# Domino_Pi.net
KiCad netlist of a schematic drawn in EAGLE
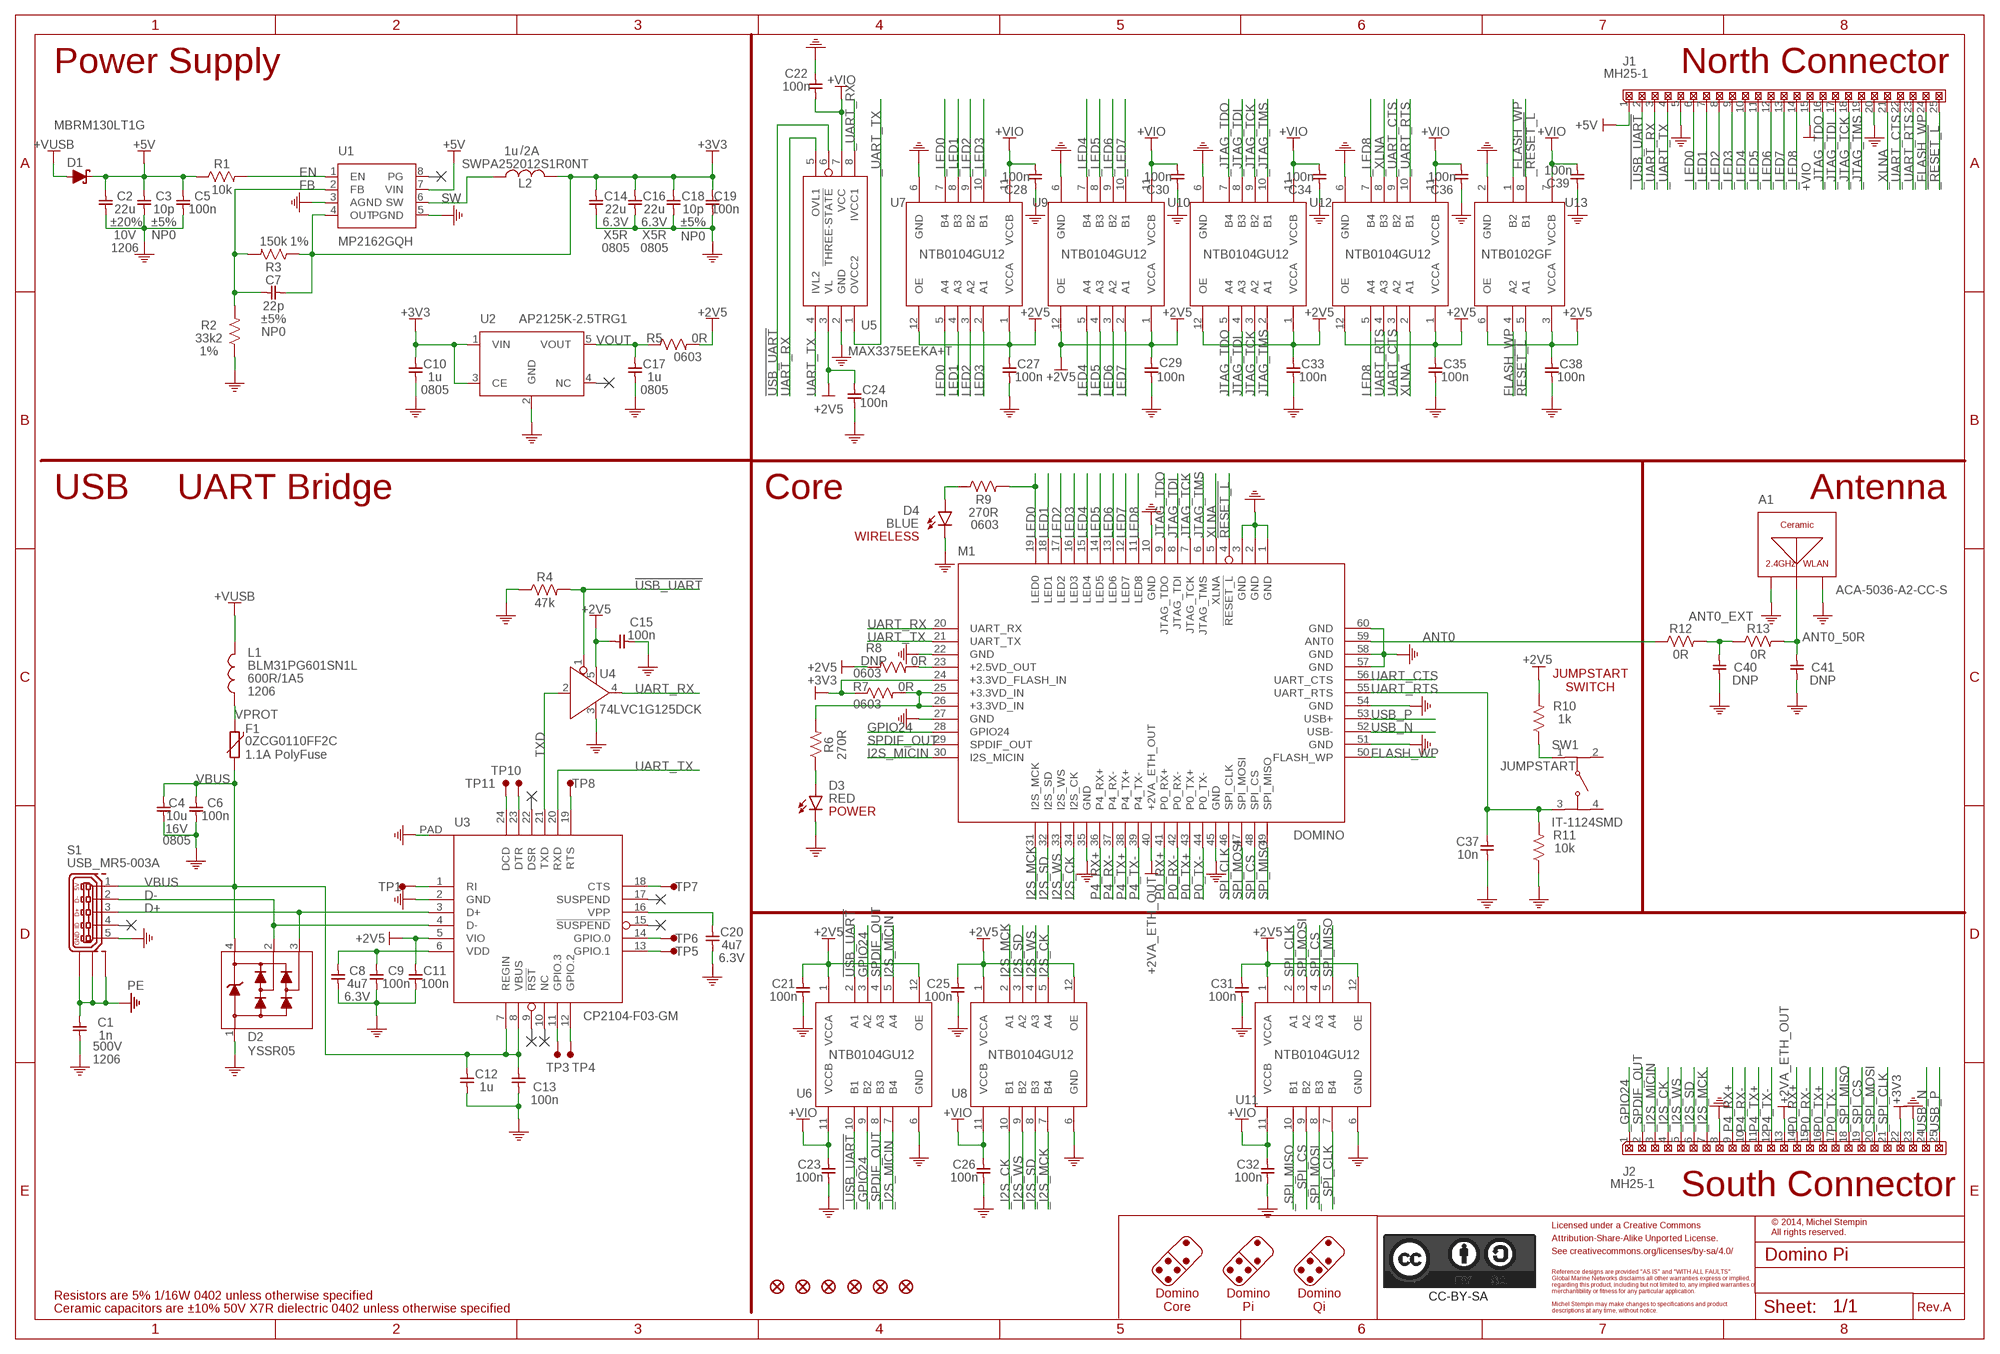
[diagram p0: schematic, sheet 1]

(export (version "E")
  (design (tool "Eeschema 10.0.6"))
  (components
    (comp (ref "A1")
      (value "ACA-5036-A2-CC-S")
      (footprint "eagle-import:ACA-5036-A2-CC-S")
      (libsource (lib "eagle-import") (part "ACA-5036-A2-CC-S"))
    )
    (comp (ref "C1")
      (value "1n")
      (footprint "eagle-import:C1206")
      (fields
        (field (name "SIZE") "1206")
        (field (name "PARTNO") "C1206_1n_X7R_10%_CER_500V")
        (field (name "VOLT") "500V")
      )
      (libsource (lib "eagle-import") (part "CAP_1206"))
    )
    (comp (ref "C2")
      (value "22u")
      (footprint "eagle-import:C1206")
      (fields
        (field (name "SIZE") "1206")
        (field (name "PARTNO") "C1206_22u_X7R_20%_CER_10V")
        (field (name "TOL") "±20%")
        (field (name "VOLT") "10V")
      )
      (libsource (lib "eagle-import") (part "CAP_1206"))
    )
    (comp (ref "C3")
      (value "10p")
      (footprint "eagle-import:C0402")
      (fields
        (field (name "PARTNO") "C0402_10p_NP0_5%_CER_50V")
        (field (name "TC") "NP0")
        (field (name "TOL") "±5%")
      )
      (libsource (lib "eagle-import") (part "CAP_0402"))
    )
    (comp (ref "C4")
      (value "10u")
      (footprint "eagle-import:C0805")
      (fields
        (field (name "SIZE") "0805")
        (field (name "PARTNO") "C0805_10u_X7R_10%_CER_16V")
        (field (name "VOLT") "16V")
      )
      (libsource (lib "eagle-import") (part "CAP_0805"))
    )
    (comp (ref "C5")
      (value "100n")
      (footprint "eagle-import:C0402")
      (fields (field (name "PARTNO") "C0402_100n_X7R_10%_CER_50V"))
      (libsource (lib "eagle-import") (part "CAP_0402"))
    )
    (comp (ref "C6")
      (value "100n")
      (footprint "eagle-import:C0402")
      (fields (field (name "PARTNO") "C0402_100n_X7R_10%_CER_50V"))
      (libsource (lib "eagle-import") (part "CAP_0402"))
    )
    (comp (ref "C7")
      (value "22p")
      (footprint "eagle-import:C0402")
      (fields
        (field (name "PARTNO") "C0402_22p_NP0_5%_CER_50V")
        (field (name "TC") "NP0")
        (field (name "TOL") "±5%")
      )
      (libsource (lib "eagle-import") (part "CAP_0402"))
    )
    (comp (ref "C8")
      (value "4u7")
      (footprint "eagle-import:C0402")
      (fields (field (name "PARTNO") "C0402_4u7_X7R_10%_CER_6V3") (field (name "VOLT") "6.3V"))
      (libsource (lib "eagle-import") (part "CAP_0402"))
    )
    (comp (ref "C9")
      (value "100n")
      (footprint "eagle-import:C0402")
      (fields (field (name "PARTNO") "C0402_100n_X7R_10%_CER_50V"))
      (libsource (lib "eagle-import") (part "CAP_0402"))
    )
    (comp (ref "C10")
      (value "1u")
      (footprint "eagle-import:C0805")
      (fields (field (name "SIZE") "0805") (field (name "PARTNO") "C0805_1u_X7R_10%_CER_50V"))
      (libsource (lib "eagle-import") (part "CAP_0805"))
    )
    (comp (ref "C11")
      (value "100n")
      (footprint "eagle-import:C0402")
      (fields (field (name "PARTNO") "C0402_100n_X7R_10%_CER_50V"))
      (libsource (lib "eagle-import") (part "CAP_0402"))
    )
    (comp (ref "C12")
      (value "1u")
      (footprint "eagle-import:C0402")
      (fields (field (name "PARTNO") "C0402_1u_X7R_10%_CER_50V"))
      (libsource (lib "eagle-import") (part "CAP_0402"))
    )
    (comp (ref "C13")
      (value "100n")
      (footprint "eagle-import:C0402")
      (fields (field (name "PARTNO") "C0402_100n_X7R_10%_CER_50V"))
      (libsource (lib "eagle-import") (part "CAP_0402"))
    )
    (comp (ref "C14")
      (value "22u")
      (footprint "eagle-import:C0805")
      (fields
        (field (name "SIZE") "0805")
        (field (name "PARTNO") "C0805_22u_X5R_20%_CER_6V3")
        (field (name "TC") "X5R")
        (field (name "VOLT") "6.3V")
      )
      (libsource (lib "eagle-import") (part "CAP_0805"))
    )
    (comp (ref "C15")
      (value "100n")
      (footprint "eagle-import:C0402")
      (fields (field (name "PARTNO") "C0402_100n_X7R_10%_CER_50V"))
      (libsource (lib "eagle-import") (part "CAP_0402"))
    )
    (comp (ref "C16")
      (value "22u")
      (footprint "eagle-import:C0805")
      (fields
        (field (name "SIZE") "0805")
        (field (name "PARTNO") "C0805_22u_X5R_20%_CER_6V3")
        (field (name "TC") "X5R")
        (field (name "VOLT") "6.3V")
      )
      (libsource (lib "eagle-import") (part "CAP_0805"))
    )
    (comp (ref "C17")
      (value "1u")
      (footprint "eagle-import:C0805")
      (fields (field (name "SIZE") "0805") (field (name "PARTNO") "C0805_1u_X7R_10%_CER_50V"))
      (libsource (lib "eagle-import") (part "CAP_0805"))
    )
    (comp (ref "C18")
      (value "10p")
      (footprint "eagle-import:C0402")
      (fields
        (field (name "PARTNO") "C0402_10p_NP0_5%_CER_50V")
        (field (name "TC") "NP0")
        (field (name "TOL") "±5%")
      )
      (libsource (lib "eagle-import") (part "CAP_0402"))
    )
    (comp (ref "C19")
      (value "100n")
      (footprint "eagle-import:C0402")
      (fields (field (name "PARTNO") "C0402_100n_X7R_10%_CER_50V"))
      (libsource (lib "eagle-import") (part "CAP_0402"))
    )
    (comp (ref "C20")
      (value "4u7")
      (footprint "eagle-import:C0402")
      (fields (field (name "PARTNO") "C0402_4u7_X7R_10%_CER_6V3") (field (name "VOLT") "6.3V"))
      (libsource (lib "eagle-import") (part "CAP_0402"))
    )
    (comp (ref "C21")
      (value "100n")
      (footprint "eagle-import:C0402")
      (fields (field (name "PARTNO") "C0402_100n_X7R_10%_CER_50V"))
      (libsource (lib "eagle-import") (part "CAP_0402"))
    )
    (comp (ref "C22")
      (value "100n")
      (footprint "eagle-import:C0402")
      (fields (field (name "PARTNO") "C0402_100n_X7R_10%_CER_50V"))
      (libsource (lib "eagle-import") (part "CAP_0402"))
    )
    (comp (ref "C23")
      (value "100n")
      (footprint "eagle-import:C0402")
      (fields (field (name "PARTNO") "C0402_100n_X7R_10%_CER_50V"))
      (libsource (lib "eagle-import") (part "CAP_0402"))
    )
    (comp (ref "C24")
      (value "100n")
      (footprint "eagle-import:C0402")
      (fields (field (name "PARTNO") "C0402_100n_X7R_10%_CER_50V"))
      (libsource (lib "eagle-import") (part "CAP_0402"))
    )
    (comp (ref "C25")
      (value "100n")
      (footprint "eagle-import:C0402")
      (fields (field (name "PARTNO") "C0402_100n_X7R_10%_CER_50V"))
      (libsource (lib "eagle-import") (part "CAP_0402"))
    )
    (comp (ref "C26")
      (value "100n")
      (footprint "eagle-import:C0402")
      (fields (field (name "PARTNO") "C0402_100n_X7R_10%_CER_50V"))
      (libsource (lib "eagle-import") (part "CAP_0402"))
    )
    (comp (ref "C27")
      (value "100n")
      (footprint "eagle-import:C0402")
      (fields (field (name "PARTNO") "C0402_100n_X7R_10%_CER_50V"))
      (libsource (lib "eagle-import") (part "CAP_0402"))
    )
    (comp (ref "C28")
      (value "100n")
      (footprint "eagle-import:C0402")
      (fields (field (name "PARTNO") "C0402_100n_X7R_10%_CER_50V"))
      (libsource (lib "eagle-import") (part "CAP_0402"))
    )
    (comp (ref "C29")
      (value "100n")
      (footprint "eagle-import:C0402")
      (fields (field (name "PARTNO") "C0402_100n_X7R_10%_CER_50V"))
      (libsource (lib "eagle-import") (part "CAP_0402"))
    )
    (comp (ref "C30")
      (value "100n")
      (footprint "eagle-import:C0402")
      (fields (field (name "PARTNO") "C0402_100n_X7R_10%_CER_50V"))
      (libsource (lib "eagle-import") (part "CAP_0402"))
    )
    (comp (ref "C31")
      (value "100n")
      (footprint "eagle-import:C0402")
      (fields (field (name "PARTNO") "C0402_100n_X7R_10%_CER_50V"))
      (libsource (lib "eagle-import") (part "CAP_0402"))
    )
    (comp (ref "C32")
      (value "100n")
      (footprint "eagle-import:C0402")
      (fields (field (name "PARTNO") "C0402_100n_X7R_10%_CER_50V"))
      (libsource (lib "eagle-import") (part "CAP_0402"))
    )
    (comp (ref "C33")
      (value "100n")
      (footprint "eagle-import:C0402")
      (fields (field (name "PARTNO") "C0402_100n_X7R_10%_CER_50V"))
      (libsource (lib "eagle-import") (part "CAP_0402"))
    )
    (comp (ref "C34")
      (value "100n")
      (footprint "eagle-import:C0402")
      (fields (field (name "PARTNO") "C0402_100n_X7R_10%_CER_50V"))
      (libsource (lib "eagle-import") (part "CAP_0402"))
    )
    (comp (ref "C35")
      (value "100n")
      (footprint "eagle-import:C0402")
      (fields (field (name "PARTNO") "C0402_100n_X7R_10%_CER_50V"))
      (libsource (lib "eagle-import") (part "CAP_0402"))
    )
    (comp (ref "C36")
      (value "100n")
      (footprint "eagle-import:C0402")
      (fields (field (name "PARTNO") "C0402_100n_X7R_10%_CER_50V"))
      (libsource (lib "eagle-import") (part "CAP_0402"))
    )
    (comp (ref "C37")
      (value "10n")
      (footprint "eagle-import:C0402")
      (fields (field (name "PARTNO") "C0402_10n_X7R_10%_CER_50V"))
      (libsource (lib "eagle-import") (part "CAP_0402"))
    )
    (comp (ref "C38")
      (value "100n")
      (footprint "eagle-import:C0402")
      (fields (field (name "PARTNO") "C0402_100n_X7R_10%_CER_50V"))
      (libsource (lib "eagle-import") (part "CAP_0402"))
    )
    (comp (ref "C39")
      (value "100n")
      (footprint "eagle-import:C0402")
      (fields (field (name "PARTNO") "C0402_100n_X7R_10%_CER_50V"))
      (libsource (lib "eagle-import") (part "CAP_0402"))
    )
    (comp (ref "C40")
      (value "DNP")
      (footprint "eagle-import:C0402")
      (fields (field (name "PARTNO") "C0402_DNP"))
      (libsource (lib "eagle-import") (part "CAP_0402"))
    )
    (comp (ref "C41")
      (value "DNP")
      (footprint "eagle-import:C0402")
      (fields (field (name "PARTNO") "C0402_DNP"))
      (libsource (lib "eagle-import") (part "CAP_0402"))
    )
    (comp (ref "CC-BY-SA")
      (value "CC-BY-SA_LOGO")
      (footprint "eagle-import:CC-BY-SA_LOGO")
      (libsource (lib "eagle-import") (part "CC-BY-SA_LOGO"))
    )
    (comp (ref "D1")
      (value "MBRM130LT1G")
      (footprint "eagle-import:DO-216AA")
      (libsource (lib "eagle-import") (part "MBRM130LT1G"))
    )
    (comp (ref "D2")
      (value "YSSR05")
      (footprint "eagle-import:SOT143B")
      (libsource (lib "eagle-import") (part "YSSR05"))
    )
    (comp (ref "D3")
      (value "RED")
      (footprint "eagle-import:LED0603")
      (fields (field (name "PARTNO") "LED0603-RED"))
      (libsource (lib "eagle-import") (part "LED_0603"))
    )
    (comp (ref "D4")
      (value "BLUE")
      (footprint "eagle-import:LED0603")
      (fields (field (name "PARTNO") "LED0603-BLUE"))
      (libsource (lib "eagle-import") (part "LED_0603"))
    )
    (comp (ref "F1")
      (value "0ZCG0110FF2C")
      (footprint "eagle-import:PTC1812")
      (fields (field (name "RATE") "1.1A"))
      (libsource (lib "eagle-import") (part "0ZCG0110FF2C"))
    )
    (comp (ref "F2")
      (value "FIDUCIAL")
      (footprint "eagle-import:FIDUCIAL")
      (libsource (lib "eagle-import") (part "FIDUCIAL"))
    )
    (comp (ref "F3")
      (value "FIDUCIAL")
      (footprint "eagle-import:FIDUCIAL")
      (libsource (lib "eagle-import") (part "FIDUCIAL"))
    )
    (comp (ref "F4")
      (value "FIDUCIAL")
      (footprint "eagle-import:FIDUCIAL")
      (libsource (lib "eagle-import") (part "FIDUCIAL"))
    )
    (comp (ref "F5")
      (value "FIDUCIAL")
      (footprint "eagle-import:FIDUCIAL")
      (libsource (lib "eagle-import") (part "FIDUCIAL"))
    )
    (comp (ref "F6")
      (value "FIDUCIAL")
      (footprint "eagle-import:FIDUCIAL")
      (libsource (lib "eagle-import") (part "FIDUCIAL"))
    )
    (comp (ref "F7")
      (value "FIDUCIAL")
      (footprint "eagle-import:FIDUCIAL")
      (libsource (lib "eagle-import") (part "FIDUCIAL"))
    )
    (comp (ref "J1")
      (value "MH25-1")
      (footprint "eagle-import:MH25-1-0.1")
      (fields (field (name "PARTNO") "MH25-1-0.1"))
      (libsource (lib "eagle-import") (part "MH25-1"))
    )
    (comp (ref "J2")
      (value "MH25-1")
      (footprint "eagle-import:MH25-1-0.1")
      (fields (field (name "PARTNO") "MH25-1-0.1"))
      (libsource (lib "eagle-import") (part "MH25-1"))
    )
    (comp (ref "L1")
      (value "BLM31PG601SN1L")
      (footprint "eagle-import:FB1206")
      (fields (field (name "SIZE") "1206") (field (name "OPT") "600R/1A5"))
      (libsource (lib "eagle-import") (part "FB_1206"))
    )
    (comp (ref "L2")
      (value "SWPA252012S1R0NT")
      (footprint "eagle-import:SWPA252012S")
      (fields
        (field (name "INDUCTANCE") "1u")
        (field (name "RATE") "2A")
        (field (name "PARTNO") "SWPA252012SMT")
        (field (name "RATE_1") "2A")
      )
      (libsource (lib "eagle-import") (part "SWPA252012S?NT1R0"))
    )
    (comp (ref "M1")
      (value "DOMINO")
      (footprint "eagle-import:DOMINO")
      (fields (field (name "PARTNO") "DOMINO-CORE"))
      (libsource (lib "eagle-import") (part "DOMINO"))
    )
    (comp (ref "R1")
      (value "10k")
      (footprint "eagle-import:R0402")
      (fields (field (name "PARTNO") "R0402_10k_5%_62.5mW"))
      (libsource (lib "eagle-import") (part "RES_0402"))
    )
    (comp (ref "R2")
      (value "33k2")
      (footprint "eagle-import:R0402")
      (fields (field (name "PARTNO") "R0402_33k2_1%_62.5mW") (field (name "TOL") "1%"))
      (libsource (lib "eagle-import") (part "RES_0402"))
    )
    (comp (ref "R3")
      (value "150k")
      (footprint "eagle-import:R0402")
      (fields (field (name "PARTNO") "R0402_150k_1%_62.5mW") (field (name "TOL") "1%"))
      (libsource (lib "eagle-import") (part "RES_0402"))
    )
    (comp (ref "R4")
      (value "47k")
      (footprint "eagle-import:R0402")
      (fields (field (name "PARTNO") "R0402_47k_5%_62.5mW"))
      (libsource (lib "eagle-import") (part "RES_0402"))
    )
    (comp (ref "R5")
      (value "0R")
      (footprint "eagle-import:R0603")
      (fields (field (name "SIZE") "0603") (field (name "PARTNO") "R0603_0R_5%_125mW"))
      (libsource (lib "eagle-import") (part "RES_0603"))
    )
    (comp (ref "R6")
      (value "270R")
      (footprint "eagle-import:R0402")
      (fields (field (name "PARTNO") "R0603_270R_5%_125mW"))
      (libsource (lib "eagle-import") (part "RES_0402"))
    )
    (comp (ref "R7")
      (value "0R")
      (footprint "eagle-import:R0603")
      (fields (field (name "SIZE") "0603") (field (name "PARTNO") "R0603_0R_5%_125mW"))
      (libsource (lib "eagle-import") (part "RES_0603"))
    )
    (comp (ref "R8")
      (value "0R")
      (footprint "eagle-import:R0603")
      (fields (field (name "SIZE") "0603") (field (name "PARTNO") "R0603_0R_5%_125mW"))
      (libsource (lib "eagle-import") (part "RES_0603"))
    )
    (comp (ref "R9")
      (value "270R")
      (footprint "eagle-import:R0603")
      (fields (field (name "SIZE") "0603") (field (name "PARTNO") "R0603_270R_5%_125mW"))
      (libsource (lib "eagle-import") (part "RES_0603"))
    )
    (comp (ref "R10")
      (value "1k")
      (footprint "eagle-import:R0402")
      (fields (field (name "PARTNO") "R0402_1k_5%_62.5mW"))
      (libsource (lib "eagle-import") (part "RES_0402"))
    )
    (comp (ref "R11")
      (value "10k")
      (footprint "eagle-import:R0402")
      (fields (field (name "PARTNO") "R0402_10k_5%_62.5mW"))
      (libsource (lib "eagle-import") (part "RES_0402"))
    )
    (comp (ref "R12")
      (value "0R")
      (footprint "eagle-import:R0402")
      (fields (field (name "PARTNO") "R0402_0R_5%_62.5mW"))
      (libsource (lib "eagle-import") (part "RES_0402"))
    )
    (comp (ref "R13")
      (value "0R")
      (footprint "eagle-import:R0402")
      (fields (field (name "PARTNO") "R0402_0R_5%_62.5mW"))
      (libsource (lib "eagle-import") (part "RES_0402"))
    )
    (comp (ref "S1")
      (value "USB_MR5-003A")
      (footprint "eagle-import:USB_MR5-003A")
      (fields (field (name "PARTNO") "USB MR5-003A"))
      (libsource (lib "eagle-import") (part "USB_MR5-003A"))
    )
    (comp (ref "SW1")
      (value "IT-1124SMD")
      (footprint "eagle-import:IT-1124SMD")
      (libsource (lib "eagle-import") (part "IT-1124SMD"))
    )
    (comp (ref "TP1")
      (value "TEST_PAD")
      (footprint "eagle-import:TEST_PAD")
      (libsource (lib "eagle-import") (part "TEST_PAD"))
    )
    (comp (ref "TP3")
      (value "TEST_PAD")
      (footprint "eagle-import:TEST_PAD")
      (libsource (lib "eagle-import") (part "TEST_PAD"))
    )
    (comp (ref "TP4")
      (value "TEST_PAD")
      (footprint "eagle-import:TEST_PAD")
      (libsource (lib "eagle-import") (part "TEST_PAD"))
    )
    (comp (ref "TP5")
      (value "TEST_PAD")
      (footprint "eagle-import:TEST_PAD")
      (libsource (lib "eagle-import") (part "TEST_PAD"))
    )
    (comp (ref "TP6")
      (value "TEST_PAD")
      (footprint "eagle-import:TEST_PAD")
      (libsource (lib "eagle-import") (part "TEST_PAD"))
    )
    (comp (ref "TP7")
      (value "TEST_PAD")
      (footprint "eagle-import:TEST_PAD")
      (libsource (lib "eagle-import") (part "TEST_PAD"))
    )
    (comp (ref "TP8")
      (value "TEST_PAD")
      (footprint "eagle-import:TEST_PAD")
      (libsource (lib "eagle-import") (part "TEST_PAD"))
    )
    (comp (ref "TP10")
      (value "TEST_PAD")
      (footprint "eagle-import:TEST_PAD")
      (libsource (lib "eagle-import") (part "TEST_PAD"))
    )
    (comp (ref "TP11")
      (value "TEST_PAD")
      (footprint "eagle-import:TEST_PAD")
      (libsource (lib "eagle-import") (part "TEST_PAD"))
    )
    (comp (ref "U1")
      (value "MP2162GQH")
      (footprint "eagle-import:QFN-8_2X1.5")
      (libsource (lib "eagle-import") (part "MP2162GQH"))
    )
    (comp (ref "U2")
      (value "AP2125K-2.5TRG1")
      (footprint "eagle-import:SOT23-5")
      (libsource (lib "eagle-import") (part "AP2125?K-2.5TRG1"))
    )
    (comp (ref "U3")
      (value "CP2104-F03-GM")
      (footprint "eagle-import:QFN-25_4X4")
      (libsource (lib "eagle-import") (part "CP2104-F03-GM"))
    )
    (comp (ref "U4")
      (value "74LVC1G125DCK")
      (footprint "eagle-import:SC70")
      (fields (field (name "PARTNO") "74LVC1G125DCK "))
      (libsource (lib "eagle-import") (part "741G125DCKLVC"))
    )
    (comp (ref "U5")
      (value "MAX3375EEKA+T")
      (footprint "eagle-import:SOT23-8")
      (libsource (lib "eagle-import") (part "MAX3375EEKA+T"))
    )
    (comp (ref "U6")
      (value "NTB0104GU12")
      (footprint "eagle-import:XQFN-12")
      (libsource (lib "eagle-import") (part "NTB0104GU12"))
    )
    (comp (ref "U7")
      (value "NTB0104GU12")
      (footprint "eagle-import:XQFN-12")
      (libsource (lib "eagle-import") (part "NTB0104GU12"))
    )
    (comp (ref "U8")
      (value "NTB0104GU12")
      (footprint "eagle-import:XQFN-12")
      (libsource (lib "eagle-import") (part "NTB0104GU12"))
    )
    (comp (ref "U9")
      (value "NTB0104GU12")
      (footprint "eagle-import:XQFN-12")
      (libsource (lib "eagle-import") (part "NTB0104GU12"))
    )
    (comp (ref "U10")
      (value "NTB0104GU12")
      (footprint "eagle-import:XQFN-12")
      (libsource (lib "eagle-import") (part "NTB0104GU12"))
    )
    (comp (ref "U11")
      (value "NTB0104GU12")
      (footprint "eagle-import:XQFN-12")
      (libsource (lib "eagle-import") (part "NTB0104GU12"))
    )
    (comp (ref "U12")
      (value "NTB0104GU12")
      (footprint "eagle-import:XQFN-12")
      (libsource (lib "eagle-import") (part "NTB0104GU12"))
    )
    (comp (ref "U13")
      (value "NTB0102GF")
      (footprint "eagle-import:SOT1089")
      (libsource (lib "eagle-import") (part "NTB0102GF"))
    )
  )
  (nets
    (net (code "1") (name "+2V5") (class "Default")
      (node (ref "C11") (pin "1") (pinfunction "1_1") (pintype "passive"))
      (node (ref "C15") (pin "2") (pinfunction "2_2") (pintype "passive"))
      (node (ref "C21") (pin "1") (pinfunction "1_1") (pintype "passive"))
      (node (ref "C24") (pin "2") (pinfunction "2_2") (pintype "passive"))
      (node (ref "C25") (pin "1") (pinfunction "1_1") (pintype "passive"))
      (node (ref "C27") (pin "2") (pinfunction "2_2") (pintype "passive"))
      (node (ref "C29") (pin "2") (pinfunction "2_2") (pintype "passive"))
      (node (ref "C31") (pin "1") (pinfunction "1_1") (pintype "passive"))
      (node (ref "C33") (pin "2") (pinfunction "2_2") (pintype "passive"))
      (node (ref "C35") (pin "2") (pinfunction "2_2") (pintype "passive"))
      (node (ref "C38") (pin "2") (pinfunction "2_2") (pintype "passive"))
      (node (ref "R10") (pin "2") (pinfunction "2_2") (pintype "passive"))
      (node (ref "R5") (pin "2") (pinfunction "2_2") (pintype "passive"))
      (node (ref "R8") (pin "1") (pinfunction "1_1") (pintype "passive"))
      (node (ref "U10") (pin "1") (pinfunction "VCCA_1") (pintype "power_in"))
      (node (ref "U10") (pin "12") (pinfunction "OE_12") (pintype "input"))
      (node (ref "U11") (pin "1") (pinfunction "VCCA_1") (pintype "power_in"))
      (node (ref "U11") (pin "12") (pinfunction "OE_12") (pintype "input"))
      (node (ref "U12") (pin "1") (pinfunction "VCCA_1") (pintype "power_in"))
      (node (ref "U12") (pin "12") (pinfunction "OE_12") (pintype "input"))
      (node (ref "U13") (pin "3") (pinfunction "VCCA_3") (pintype "power_in"))
      (node (ref "U13") (pin "6") (pinfunction "OE_6") (pintype "input"))
      (node (ref "U3") (pin "5") (pinfunction "VIO_5") (pintype "power_in"))
      (node (ref "U4") (pin "5") (pinfunction "VCC_5") (pintype "power_in"))
      (node (ref "U5") (pin "3") (pinfunction "VL_3") (pintype "power_in"))
      (node (ref "U6") (pin "1") (pinfunction "VCCA_1") (pintype "power_in"))
      (node (ref "U6") (pin "12") (pinfunction "OE_12") (pintype "input"))
      (node (ref "U7") (pin "1") (pinfunction "VCCA_1") (pintype "power_in"))
      (node (ref "U7") (pin "12") (pinfunction "OE_12") (pintype "input"))
      (node (ref "U8") (pin "1") (pinfunction "VCCA_1") (pintype "power_in"))
      (node (ref "U8") (pin "12") (pinfunction "OE_12") (pintype "input"))
      (node (ref "U9") (pin "1") (pinfunction "VCCA_1") (pintype "power_in"))
      (node (ref "U9") (pin "12") (pinfunction "OE_12") (pintype "input"))
    )
    (net (code "2") (name "+2VA_ETH_OUT") (class "Default")
      (node (ref "J2") (pin "13") (pinfunction "13_13") (pintype "passive"))
      (node (ref "M1") (pin "40") (pinfunction "+2VA_ETH_OUT_40") (pintype "power_in"))
    )
    (net (code "3") (name "+3V3") (class "Default")
      (node (ref "C10") (pin "1") (pinfunction "1_1") (pintype "passive"))
      (node (ref "C14") (pin "1") (pinfunction "1_1") (pintype "passive"))
      (node (ref "C16") (pin "1") (pinfunction "1_1") (pintype "passive"))
      (node (ref "C18") (pin "1") (pinfunction "1_1") (pintype "passive"))
      (node (ref "C19") (pin "1") (pinfunction "1_1") (pintype "passive"))
      (node (ref "C7") (pin "2") (pinfunction "2_2") (pintype "passive"))
      (node (ref "J2") (pin "22") (pinfunction "22_22") (pintype "passive"))
      (node (ref "L2") (pin "2") (pinfunction "2_2") (pintype "passive"))
      (node (ref "M1") (pin "24") (pinfunction "+3.3VD_FLASH_IN_24") (pintype "power_in"))
      (node (ref "R3") (pin "1") (pinfunction "1_1") (pintype "passive"))
      (node (ref "R7") (pin "1") (pinfunction "1_1") (pintype "passive"))
      (node (ref "U1") (pin "4") (pinfunction "OUT_4") (pintype "power_in"))
      (node (ref "U2") (pin "1") (pinfunction "VIN_1") (pintype "power_in"))
      (node (ref "U2") (pin "3") (pinfunction "CE_3") (pintype "input"))
    )
    (net (code "4") (name "+5V") (class "Default")
      (node (ref "C2") (pin "1") (pinfunction "1_1") (pintype "passive"))
      (node (ref "C3") (pin "1") (pinfunction "1_1") (pintype "passive"))
      (node (ref "C5") (pin "1") (pinfunction "1_1") (pintype "passive"))
      (node (ref "D1") (pin "1") (pinfunction "C_1") (pintype "passive"))
      (node (ref "J1") (pin "1") (pinfunction "1_1") (pintype "passive"))
      (node (ref "R1") (pin "1") (pinfunction "1_1") (pintype "passive"))
      (node (ref "U1") (pin "7") (pinfunction "VIN_7") (pintype "power_in"))
    )
    (net (code "5") (name "+VIO") (class "Default")
      (node (ref "C22") (pin "1") (pinfunction "1_1") (pintype "passive"))
      (node (ref "C23") (pin "1") (pinfunction "1_1") (pintype "passive"))
      (node (ref "C26") (pin "1") (pinfunction "1_1") (pintype "passive"))
      (node (ref "C28") (pin "1") (pinfunction "1_1") (pintype "passive"))
      (node (ref "C30") (pin "1") (pinfunction "1_1") (pintype "passive"))
      (node (ref "C32") (pin "1") (pinfunction "1_1") (pintype "passive"))
      (node (ref "C34") (pin "1") (pinfunction "1_1") (pintype "passive"))
      (node (ref "C36") (pin "1") (pinfunction "1_1") (pintype "passive"))
      (node (ref "C39") (pin "1") (pinfunction "1_1") (pintype "passive"))
      (node (ref "J1") (pin "15") (pinfunction "15_15") (pintype "passive"))
      (node (ref "U10") (pin "11") (pinfunction "VCCB_11") (pintype "power_in"))
      (node (ref "U11") (pin "11") (pinfunction "VCCB_11") (pintype "power_in"))
      (node (ref "U12") (pin "11") (pinfunction "VCCB_11") (pintype "power_in"))
      (node (ref "U13") (pin "7") (pinfunction "VCCB_7") (pintype "power_in"))
      (node (ref "U5") (pin "7") (pinfunction "VCC_7") (pintype "power_in"))
      (node (ref "U6") (pin "11") (pinfunction "VCCB_11") (pintype "power_in"))
      (node (ref "U7") (pin "11") (pinfunction "VCCB_11") (pintype "power_in"))
      (node (ref "U8") (pin "11") (pinfunction "VCCB_11") (pintype "power_in"))
      (node (ref "U9") (pin "11") (pinfunction "VCCB_11") (pintype "power_in"))
    )
    (net (code "6") (name "+VUSB") (class "Default")
      (node (ref "D1") (pin "2") (pinfunction "A_2") (pintype "passive"))
      (node (ref "L1") (pin "1") (pinfunction "1_1") (pintype "passive"))
    )
    (net (code "7") (name "/ANT0") (class "Default")
      (node (ref "M1") (pin "59") (pinfunction "ANT0_59") (pintype "passive"))
      (node (ref "R12") (pin "1") (pinfunction "1_1") (pintype "passive"))
    )
    (net (code "8") (name "/ANT0_50R") (class "Default")
      (node (ref "A1") (pin "FEED") (pinfunction "A_FEED") (pintype "passive"))
      (node (ref "C41") (pin "1") (pinfunction "1_1") (pintype "passive"))
      (node (ref "R13") (pin "2") (pinfunction "2_2") (pintype "passive"))
    )
    (net (code "9") (name "/ANT0_EXT") (class "Default")
      (node (ref "C40") (pin "1") (pinfunction "1_1") (pintype "passive"))
      (node (ref "R12") (pin "2") (pinfunction "2_2") (pintype "passive"))
      (node (ref "R13") (pin "1") (pinfunction "1_1") (pintype "passive"))
    )
    (net (code "10") (name "/D+") (class "Default")
      (node (ref "D2") (pin "3") (pinfunction "P$3_3") (pintype "passive"))
      (node (ref "S1") (pin "3") (pinfunction "3_3") (pintype "passive"))
      (node (ref "U3") (pin "3") (pinfunction "D+_3") (pintype "passive"))
    )
    (net (code "11") (name "/D-") (class "Default")
      (node (ref "D2") (pin "2") (pinfunction "P$2_2") (pintype "passive"))
      (node (ref "S1") (pin "2") (pinfunction "2_2") (pintype "passive"))
      (node (ref "U3") (pin "4") (pinfunction "D-_4") (pintype "passive"))
    )
    (net (code "12") (name "/EN") (class "Default")
      (node (ref "R1") (pin "2") (pinfunction "2_2") (pintype "passive"))
      (node (ref "U1") (pin "1") (pinfunction "EN_1") (pintype "input"))
    )
    (net (code "13") (name "/FB") (class "Default")
      (node (ref "C7") (pin "1") (pinfunction "1_1") (pintype "passive"))
      (node (ref "R2") (pin "2") (pinfunction "2_2") (pintype "passive"))
      (node (ref "R3") (pin "2") (pinfunction "2_2") (pintype "passive"))
      (node (ref "U1") (pin "2") (pinfunction "FB_2") (pintype "passive"))
    )
    (net (code "14") (name "/FLASH_WP") (class "Default")
      (node (ref "M1") (pin "50") (pinfunction "FLASH_WP_50") (pintype "bidirectional"))
      (node (ref "U13") (pin "4") (pinfunction "A2_4") (pintype "bidirectional"))
    )
    (net (code "15") (name "/GPIO24") (class "Default")
      (node (ref "M1") (pin "28") (pinfunction "GPIO24_28") (pintype "bidirectional"))
      (node (ref "U6") (pin "3") (pinfunction "A2_3") (pintype "bidirectional"))
    )
    (net (code "16") (name "/I2S_CK") (class "Default")
      (node (ref "M1") (pin "34") (pinfunction "I2S_CK_34") (pintype "bidirectional"))
      (node (ref "U8") (pin "5") (pinfunction "A4_5") (pintype "bidirectional"))
    )
    (net (code "17") (name "/I2S_MCK") (class "Default")
      (node (ref "M1") (pin "31") (pinfunction "I2S_MCK_31") (pintype "bidirectional"))
      (node (ref "U8") (pin "2") (pinfunction "A1_2") (pintype "bidirectional"))
    )
    (net (code "18") (name "/I2S_MICIN") (class "Default")
      (node (ref "M1") (pin "30") (pinfunction "I2S_MICIN_30") (pintype "bidirectional"))
      (node (ref "U6") (pin "5") (pinfunction "A4_5") (pintype "bidirectional"))
    )
    (net (code "19") (name "/I2S_SD") (class "Default")
      (node (ref "M1") (pin "32") (pinfunction "I2S_SD_32") (pintype "bidirectional"))
      (node (ref "U8") (pin "3") (pinfunction "A2_3") (pintype "bidirectional"))
    )
    (net (code "20") (name "/I2S_WS") (class "Default")
      (node (ref "M1") (pin "33") (pinfunction "I2S_WS_33") (pintype "bidirectional"))
      (node (ref "U8") (pin "4") (pinfunction "A3_4") (pintype "bidirectional"))
    )
    (net (code "21") (name "/JTAG_TCK") (class "Default")
      (node (ref "M1") (pin "7") (pinfunction "JTAG_TCK_7") (pintype "bidirectional"))
      (node (ref "U10") (pin "3") (pinfunction "A2_3") (pintype "bidirectional"))
    )
    (net (code "22") (name "/JTAG_TDI") (class "Default")
      (node (ref "M1") (pin "8") (pinfunction "JTAG_TDI_8") (pintype "bidirectional"))
      (node (ref "U10") (pin "4") (pinfunction "A3_4") (pintype "bidirectional"))
    )
    (net (code "23") (name "/JTAG_TDO") (class "Default")
      (node (ref "M1") (pin "9") (pinfunction "JTAG_TDO_9") (pintype "bidirectional"))
      (node (ref "U10") (pin "5") (pinfunction "A4_5") (pintype "bidirectional"))
    )
    (net (code "24") (name "/JTAG_TMS") (class "Default")
      (node (ref "M1") (pin "6") (pinfunction "JTAG_TMS_6") (pintype "bidirectional"))
      (node (ref "U10") (pin "2") (pinfunction "A1_2") (pintype "bidirectional"))
    )
    (net (code "25") (name "/JUMPSTART") (class "Default")
      (node (ref "R10") (pin "1") (pinfunction "1_1") (pintype "passive"))
      (node (ref "SW1") (pin "1") (pinfunction "1_1") (pintype "passive"))
    )
    (net (code "26") (name "/LED0") (class "Default")
      (node (ref "M1") (pin "19") (pinfunction "LED0_19") (pintype "bidirectional"))
      (node (ref "R9") (pin "2") (pinfunction "2_2") (pintype "passive"))
      (node (ref "U7") (pin "5") (pinfunction "A4_5") (pintype "bidirectional"))
    )
    (net (code "27") (name "/LED1") (class "Default")
      (node (ref "M1") (pin "18") (pinfunction "LED1_18") (pintype "bidirectional"))
      (node (ref "U7") (pin "4") (pinfunction "A3_4") (pintype "bidirectional"))
    )
    (net (code "28") (name "/LED2") (class "Default")
      (node (ref "M1") (pin "17") (pinfunction "LED2_17") (pintype "bidirectional"))
      (node (ref "U7") (pin "3") (pinfunction "A2_3") (pintype "bidirectional"))
    )
    (net (code "29") (name "/LED3") (class "Default")
      (node (ref "M1") (pin "16") (pinfunction "LED3_16") (pintype "bidirectional"))
      (node (ref "U7") (pin "2") (pinfunction "A1_2") (pintype "bidirectional"))
    )
    (net (code "30") (name "/LED4") (class "Default")
      (node (ref "M1") (pin "15") (pinfunction "LED4_15") (pintype "bidirectional"))
      (node (ref "U9") (pin "5") (pinfunction "A4_5") (pintype "bidirectional"))
    )
    (net (code "31") (name "/LED5") (class "Default")
      (node (ref "M1") (pin "14") (pinfunction "LED5_14") (pintype "bidirectional"))
      (node (ref "U9") (pin "4") (pinfunction "A3_4") (pintype "bidirectional"))
    )
    (net (code "32") (name "/LED6") (class "Default")
      (node (ref "M1") (pin "13") (pinfunction "LED6_13") (pintype "bidirectional"))
      (node (ref "U9") (pin "3") (pinfunction "A2_3") (pintype "bidirectional"))
    )
    (net (code "33") (name "/LED7") (class "Default")
      (node (ref "M1") (pin "12") (pinfunction "LED7_12") (pintype "bidirectional"))
      (node (ref "U9") (pin "2") (pinfunction "A1_2") (pintype "bidirectional"))
    )
    (net (code "34") (name "/LED8") (class "Default")
      (node (ref "M1") (pin "11") (pinfunction "LED8_11") (pintype "bidirectional"))
      (node (ref "U12") (pin "5") (pinfunction "A4_5") (pintype "bidirectional"))
    )
    (net (code "35") (name "/P0_RX+") (class "Default")
      (node (ref "J2") (pin "14") (pinfunction "14_14") (pintype "passive"))
      (node (ref "M1") (pin "41") (pinfunction "P0_RX+_41") (pintype "passive"))
    )
    (net (code "36") (name "/P0_RX-") (class "Default")
      (node (ref "J2") (pin "15") (pinfunction "15_15") (pintype "passive"))
      (node (ref "M1") (pin "42") (pinfunction "P0_RX-_42") (pintype "passive"))
    )
    (net (code "37") (name "/P0_TX+") (class "Default")
      (node (ref "J2") (pin "16") (pinfunction "16_16") (pintype "passive"))
      (node (ref "M1") (pin "43") (pinfunction "P0_TX+_43") (pintype "passive"))
    )
    (net (code "38") (name "/P0_TX-") (class "Default")
      (node (ref "J2") (pin "17") (pinfunction "17_17") (pintype "passive"))
      (node (ref "M1") (pin "44") (pinfunction "P0_TX-_44") (pintype "passive"))
    )
    (net (code "39") (name "/P4_RX+") (class "Default")
      (node (ref "J2") (pin "9") (pinfunction "9_9") (pintype "passive"))
      (node (ref "M1") (pin "36") (pinfunction "P4_RX+_36") (pintype "passive"))
    )
    (net (code "40") (name "/P4_RX-") (class "Default")
      (node (ref "J2") (pin "10") (pinfunction "10_10") (pintype "passive"))
      (node (ref "M1") (pin "37") (pinfunction "P4_RX-_37") (pintype "passive"))
    )
    (net (code "41") (name "/P4_TX+") (class "Default")
      (node (ref "J2") (pin "11") (pinfunction "11_11") (pintype "passive"))
      (node (ref "M1") (pin "38") (pinfunction "P4_TX+_38") (pintype "passive"))
    )
    (net (code "42") (name "/P4_TX-") (class "Default")
      (node (ref "J2") (pin "12") (pinfunction "12_12") (pintype "passive"))
      (node (ref "M1") (pin "39") (pinfunction "P4_TX-_39") (pintype "passive"))
    )
    (net (code "43") (name "/SPDIF_OUT") (class "Default")
      (node (ref "M1") (pin "29") (pinfunction "SPDIF_OUT_29") (pintype "bidirectional"))
      (node (ref "U6") (pin "4") (pinfunction "A3_4") (pintype "bidirectional"))
    )
    (net (code "44") (name "/SPI_CLK") (class "Default")
      (node (ref "M1") (pin "46") (pinfunction "SPI_CLK_46") (pintype "bidirectional"))
      (node (ref "U11") (pin "2") (pinfunction "A1_2") (pintype "bidirectional"))
    )
    (net (code "45") (name "/SPI_CS") (class "Default")
      (node (ref "M1") (pin "48") (pinfunction "SPI_CS_48") (pintype "bidirectional"))
      (node (ref "U11") (pin "4") (pinfunction "A3_4") (pintype "bidirectional"))
    )
    (net (code "46") (name "/SPI_MISO") (class "Default")
      (node (ref "M1") (pin "49") (pinfunction "SPI_MISO_49") (pintype "bidirectional"))
      (node (ref "U11") (pin "5") (pinfunction "A4_5") (pintype "bidirectional"))
    )
    (net (code "47") (name "/SPI_MOSI") (class "Default")
      (node (ref "M1") (pin "47") (pinfunction "SPI_MOSI_47") (pintype "bidirectional"))
      (node (ref "U11") (pin "3") (pinfunction "A2_3") (pintype "bidirectional"))
    )
    (net (code "48") (name "/SW") (class "Default")
      (node (ref "L2") (pin "1") (pinfunction "1_1") (pintype "passive"))
      (node (ref "U1") (pin "6") (pinfunction "SW_6") (pintype "passive"))
    )
    (net (code "49") (name "/TXD") (class "Default")
      (node (ref "U3") (pin "21") (pinfunction "TXD_21") (pintype "output"))
      (node (ref "U4") (pin "2") (pinfunction "A_2") (pintype "input"))
    )
    (net (code "50") (name "/UART_CTS") (class "Default")
      (node (ref "M1") (pin "56") (pinfunction "UART_CTS_56") (pintype "bidirectional"))
      (node (ref "U12") (pin "3") (pinfunction "A2_3") (pintype "bidirectional"))
    )
    (net (code "51") (name "/UART_RTS") (class "Default")
      (node (ref "C37") (pin "1") (pinfunction "1_1") (pintype "passive"))
      (node (ref "M1") (pin "55") (pinfunction "UART_RTS_55") (pintype "bidirectional"))
      (node (ref "R11") (pin "2") (pinfunction "2_2") (pintype "passive"))
      (node (ref "SW1") (pin "3") (pinfunction "3_3") (pintype "passive"))
      (node (ref "U12") (pin "4") (pinfunction "A3_4") (pintype "bidirectional"))
    )
    (net (code "52") (name "/UART_RX") (class "Default")
      (node (ref "M1") (pin "20") (pinfunction "UART_RX_20") (pintype "bidirectional"))
      (node (ref "U4") (pin "4") (pinfunction "Y_4") (pintype "tri_state"))
      (node (ref "U5") (pin "5") (pinfunction "OVL1_5") (pintype "output"))
    )
    (net (code "53") (name "/UART_TX") (class "Default")
      (node (ref "M1") (pin "21") (pinfunction "UART_TX_21") (pintype "bidirectional"))
      (node (ref "U3") (pin "20") (pinfunction "RXD_20") (pintype "input"))
      (node (ref "U5") (pin "4") (pinfunction "IVL2_4") (pintype "input"))
    )
    (net (code "54") (name "/USB_N") (class "Default")
      (node (ref "J2") (pin "24") (pinfunction "24_24") (pintype "passive"))
      (node (ref "M1") (pin "52") (pinfunction "USB-_52") (pintype "passive"))
    )
    (net (code "55") (name "/USB_P") (class "Default")
      (node (ref "J2") (pin "25") (pinfunction "25_25") (pintype "passive"))
      (node (ref "M1") (pin "53") (pinfunction "USB+_53") (pintype "passive"))
    )
    (net (code "56") (name "/VBUS") (class "Default")
      (node (ref "C12") (pin "1") (pinfunction "1_1") (pintype "passive"))
      (node (ref "C13") (pin "1") (pinfunction "1_1") (pintype "passive"))
      (node (ref "C4") (pin "1") (pinfunction "1_1") (pintype "passive"))
      (node (ref "C6") (pin "1") (pinfunction "1_1") (pintype "passive"))
      (node (ref "D2") (pin "4") (pinfunction "P$4_4") (pintype "passive"))
      (node (ref "F1") (pin "2") (pinfunction "2_2") (pintype "passive"))
      (node (ref "S1") (pin "1") (pinfunction "1_1") (pintype "passive"))
      (node (ref "U3") (pin "7") (pinfunction "REGIN_7") (pintype "power_in"))
      (node (ref "U3") (pin "8") (pinfunction "VBUS_8") (pintype "input"))
    )
    (net (code "57") (name "/VOUT") (class "Default")
      (node (ref "C17") (pin "1") (pinfunction "1_1") (pintype "passive"))
      (node (ref "R5") (pin "1") (pinfunction "1_1") (pintype "passive"))
      (node (ref "U2") (pin "5") (pinfunction "VOUT_5") (pintype "power_in"))
    )
    (net (code "58") (name "/VPROT") (class "Default")
      (node (ref "F1") (pin "1") (pinfunction "1_1") (pintype "passive"))
      (node (ref "L1") (pin "2") (pinfunction "2_2") (pintype "passive"))
    )
    (net (code "59") (name "/XLNA") (class "Default")
      (node (ref "M1") (pin "5") (pinfunction "XLNA_5") (pintype "bidirectional"))
      (node (ref "U12") (pin "2") (pinfunction "A1_2") (pintype "bidirectional"))
    )
    (net (code "60") (name "/_FLASH_WP") (class "Default")
      (node (ref "J1") (pin "24") (pinfunction "24_24") (pintype "passive"))
      (node (ref "U13") (pin "1") (pinfunction "B2_1") (pintype "bidirectional"))
    )
    (net (code "61") (name "/_GPIO24") (class "Default")
      (node (ref "J2") (pin "1") (pinfunction "1_1") (pintype "passive"))
      (node (ref "U6") (pin "9") (pinfunction "B2_9") (pintype "bidirectional"))
    )
    (net (code "62") (name "/_I2S_CK") (class "Default")
      (node (ref "J2") (pin "4") (pinfunction "4_4") (pintype "passive"))
      (node (ref "U8") (pin "10") (pinfunction "B1_10") (pintype "bidirectional"))
    )
    (net (code "63") (name "/_I2S_MCK") (class "Default")
      (node (ref "J2") (pin "7") (pinfunction "7_7") (pintype "passive"))
      (node (ref "U8") (pin "7") (pinfunction "B4_7") (pintype "bidirectional"))
    )
    (net (code "64") (name "/_I2S_MICIN") (class "Default")
      (node (ref "J2") (pin "3") (pinfunction "3_3") (pintype "passive"))
      (node (ref "U6") (pin "7") (pinfunction "B4_7") (pintype "bidirectional"))
    )
    (net (code "65") (name "/_I2S_SD") (class "Default")
      (node (ref "J2") (pin "6") (pinfunction "6_6") (pintype "passive"))
      (node (ref "U8") (pin "8") (pinfunction "B3_8") (pintype "bidirectional"))
    )
    (net (code "66") (name "/_I2S_WS") (class "Default")
      (node (ref "J2") (pin "5") (pinfunction "5_5") (pintype "passive"))
      (node (ref "U8") (pin "9") (pinfunction "B2_9") (pintype "bidirectional"))
    )
    (net (code "67") (name "/_JTAG_TCK") (class "Default")
      (node (ref "J1") (pin "18") (pinfunction "18_18") (pintype "passive"))
      (node (ref "U10") (pin "9") (pinfunction "B2_9") (pintype "bidirectional"))
    )
    (net (code "68") (name "/_JTAG_TDI") (class "Default")
      (node (ref "J1") (pin "17") (pinfunction "17_17") (pintype "passive"))
      (node (ref "U10") (pin "8") (pinfunction "B3_8") (pintype "bidirectional"))
    )
    (net (code "69") (name "/_JTAG_TDO") (class "Default")
      (node (ref "J1") (pin "16") (pinfunction "16_16") (pintype "passive"))
      (node (ref "U10") (pin "7") (pinfunction "B4_7") (pintype "bidirectional"))
    )
    (net (code "70") (name "/_JTAG_TMS") (class "Default")
      (node (ref "J1") (pin "19") (pinfunction "19_19") (pintype "passive"))
      (node (ref "U10") (pin "10") (pinfunction "B1_10") (pintype "bidirectional"))
    )
    (net (code "71") (name "/_LED0") (class "Default")
      (node (ref "J1") (pin "6") (pinfunction "6_6") (pintype "passive"))
      (node (ref "U7") (pin "7") (pinfunction "B4_7") (pintype "bidirectional"))
    )
    (net (code "72") (name "/_LED1") (class "Default")
      (node (ref "J1") (pin "7") (pinfunction "7_7") (pintype "passive"))
      (node (ref "U7") (pin "8") (pinfunction "B3_8") (pintype "bidirectional"))
    )
    (net (code "73") (name "/_LED2") (class "Default")
      (node (ref "J1") (pin "8") (pinfunction "8_8") (pintype "passive"))
      (node (ref "U7") (pin "9") (pinfunction "B2_9") (pintype "bidirectional"))
    )
    (net (code "74") (name "/_LED3") (class "Default")
      (node (ref "J1") (pin "9") (pinfunction "9_9") (pintype "passive"))
      (node (ref "U7") (pin "10") (pinfunction "B1_10") (pintype "bidirectional"))
    )
    (net (code "75") (name "/_LED4") (class "Default")
      (node (ref "J1") (pin "10") (pinfunction "10_10") (pintype "passive"))
      (node (ref "U9") (pin "7") (pinfunction "B4_7") (pintype "bidirectional"))
    )
    (net (code "76") (name "/_LED5") (class "Default")
      (node (ref "J1") (pin "11") (pinfunction "11_11") (pintype "passive"))
      (node (ref "U9") (pin "8") (pinfunction "B3_8") (pintype "bidirectional"))
    )
    (net (code "77") (name "/_LED6") (class "Default")
      (node (ref "J1") (pin "12") (pinfunction "12_12") (pintype "passive"))
      (node (ref "U9") (pin "9") (pinfunction "B2_9") (pintype "bidirectional"))
    )
    (net (code "78") (name "/_LED7") (class "Default")
      (node (ref "J1") (pin "13") (pinfunction "13_13") (pintype "passive"))
      (node (ref "U9") (pin "10") (pinfunction "B1_10") (pintype "bidirectional"))
    )
    (net (code "79") (name "/_LED8") (class "Default")
      (node (ref "J1") (pin "14") (pinfunction "14_14") (pintype "passive"))
      (node (ref "U12") (pin "7") (pinfunction "B4_7") (pintype "bidirectional"))
    )
    (net (code "80") (name "/_SPDIF_OUT") (class "Default")
      (node (ref "J2") (pin "2") (pinfunction "2_2") (pintype "passive"))
      (node (ref "U6") (pin "8") (pinfunction "B3_8") (pintype "bidirectional"))
    )
    (net (code "81") (name "/_SPI_CLK") (class "Default")
      (node (ref "J2") (pin "21") (pinfunction "21_21") (pintype "passive"))
      (node (ref "U11") (pin "7") (pinfunction "B4_7") (pintype "bidirectional"))
    )
    (net (code "82") (name "/_SPI_CS") (class "Default")
      (node (ref "J2") (pin "19") (pinfunction "19_19") (pintype "passive"))
      (node (ref "U11") (pin "9") (pinfunction "B2_9") (pintype "bidirectional"))
    )
    (net (code "83") (name "/_SPI_MISO") (class "Default")
      (node (ref "J2") (pin "18") (pinfunction "18_18") (pintype "passive"))
      (node (ref "U11") (pin "10") (pinfunction "B1_10") (pintype "bidirectional"))
    )
    (net (code "84") (name "/_SPI_MOSI") (class "Default")
      (node (ref "J2") (pin "20") (pinfunction "20_20") (pintype "passive"))
      (node (ref "U11") (pin "8") (pinfunction "B3_8") (pintype "bidirectional"))
    )
    (net (code "85") (name "/_UART_CTS") (class "Default")
      (node (ref "J1") (pin "22") (pinfunction "22_22") (pintype "passive"))
      (node (ref "U12") (pin "9") (pinfunction "B2_9") (pintype "bidirectional"))
    )
    (net (code "86") (name "/_UART_RTS") (class "Default")
      (node (ref "J1") (pin "23") (pinfunction "23_23") (pintype "passive"))
      (node (ref "U12") (pin "10") (pinfunction "B1_10") (pintype "bidirectional"))
    )
    (net (code "87") (name "/_UART_RX") (class "Default")
      (node (ref "J1") (pin "3") (pinfunction "3_3") (pintype "passive"))
      (node (ref "U5") (pin "8") (pinfunction "IVCC1_8") (pintype "input"))
    )
    (net (code "88") (name "/_UART_TX") (class "Default")
      (node (ref "J1") (pin "4") (pinfunction "4_4") (pintype "passive"))
      (node (ref "U5") (pin "1") (pinfunction "OVCC2_1") (pintype "output"))
    )
    (net (code "89") (name "/_XLNA") (class "Default")
      (node (ref "J1") (pin "21") (pinfunction "21_21") (pintype "passive"))
      (node (ref "U12") (pin "8") (pinfunction "B3_8") (pintype "bidirectional"))
    )
    (net (code "90") (name "/~{RESET_L}") (class "Default")
      (node (ref "M1") (pin "4") (pinfunction "~{RESET_L}_4") (pintype "input"))
      (node (ref "U13") (pin "5") (pinfunction "A1_5") (pintype "bidirectional"))
    )
    (net (code "91") (name "/~{USB_UART}") (class "Default")
      (node (ref "R4") (pin "2") (pinfunction "2_2") (pintype "passive"))
      (node (ref "U4") (pin "1") (pinfunction "~{OE}_1") (pintype "input"))
      (node (ref "U5") (pin "6") (pinfunction "~{THREE-STATE}_6") (pintype "input"))
      (node (ref "U6") (pin "2") (pinfunction "A1_2") (pintype "bidirectional"))
    )
    (net (code "92") (name "/~{_RESET_L}") (class "Default")
      (node (ref "J1") (pin "25") (pinfunction "25_25") (pintype "passive"))
      (node (ref "U13") (pin "8") (pinfunction "B1_8") (pintype "bidirectional"))
    )
    (net (code "93") (name "/~{_USB_UART}") (class "Default")
      (node (ref "J1") (pin "2") (pinfunction "2_2") (pintype "passive"))
      (node (ref "U6") (pin "10") (pinfunction "B1_10") (pintype "bidirectional"))
    )
    (net (code "94") (name "GND") (class "Default")
      (node (ref "A1") (pin "GND$1") (pinfunction "GND_GND$1") (pintype "power_in"))
      (node (ref "A1") (pin "GND$2") (pinfunction "GND_GND$2") (pintype "power_in"))
      (node (ref "C1") (pin "2") (pinfunction "2_2") (pintype "passive"))
      (node (ref "C10") (pin "2") (pinfunction "2_2") (pintype "passive"))
      (node (ref "C11") (pin "2") (pinfunction "2_2") (pintype "passive"))
      (node (ref "C12") (pin "2") (pinfunction "2_2") (pintype "passive"))
      (node (ref "C13") (pin "2") (pinfunction "2_2") (pintype "passive"))
      (node (ref "C14") (pin "2") (pinfunction "2_2") (pintype "passive"))
      (node (ref "C15") (pin "1") (pinfunction "1_1") (pintype "passive"))
      (node (ref "C16") (pin "2") (pinfunction "2_2") (pintype "passive"))
      (node (ref "C17") (pin "2") (pinfunction "2_2") (pintype "passive"))
      (node (ref "C18") (pin "2") (pinfunction "2_2") (pintype "passive"))
      (node (ref "C19") (pin "2") (pinfunction "2_2") (pintype "passive"))
      (node (ref "C2") (pin "2") (pinfunction "2_2") (pintype "passive"))
      (node (ref "C20") (pin "2") (pinfunction "2_2") (pintype "passive"))
      (node (ref "C21") (pin "2") (pinfunction "2_2") (pintype "passive"))
      (node (ref "C22") (pin "2") (pinfunction "2_2") (pintype "passive"))
      (node (ref "C23") (pin "2") (pinfunction "2_2") (pintype "passive"))
      (node (ref "C24") (pin "1") (pinfunction "1_1") (pintype "passive"))
      (node (ref "C25") (pin "2") (pinfunction "2_2") (pintype "passive"))
      (node (ref "C26") (pin "2") (pinfunction "2_2") (pintype "passive"))
      (node (ref "C27") (pin "1") (pinfunction "1_1") (pintype "passive"))
      (node (ref "C28") (pin "2") (pinfunction "2_2") (pintype "passive"))
      (node (ref "C29") (pin "1") (pinfunction "1_1") (pintype "passive"))
      (node (ref "C3") (pin "2") (pinfunction "2_2") (pintype "passive"))
      (node (ref "C30") (pin "2") (pinfunction "2_2") (pintype "passive"))
      (node (ref "C31") (pin "2") (pinfunction "2_2") (pintype "passive"))
      (node (ref "C32") (pin "2") (pinfunction "2_2") (pintype "passive"))
      (node (ref "C33") (pin "1") (pinfunction "1_1") (pintype "passive"))
      (node (ref "C34") (pin "2") (pinfunction "2_2") (pintype "passive"))
      (node (ref "C35") (pin "1") (pinfunction "1_1") (pintype "passive"))
      (node (ref "C36") (pin "2") (pinfunction "2_2") (pintype "passive"))
      (node (ref "C37") (pin "2") (pinfunction "2_2") (pintype "passive"))
      (node (ref "C38") (pin "1") (pinfunction "1_1") (pintype "passive"))
      (node (ref "C39") (pin "2") (pinfunction "2_2") (pintype "passive"))
      (node (ref "C4") (pin "2") (pinfunction "2_2") (pintype "passive"))
      (node (ref "C40") (pin "2") (pinfunction "2_2") (pintype "passive"))
      (node (ref "C41") (pin "2") (pinfunction "2_2") (pintype "passive"))
      (node (ref "C5") (pin "2") (pinfunction "2_2") (pintype "passive"))
      (node (ref "C6") (pin "2") (pinfunction "2_2") (pintype "passive"))
      (node (ref "C8") (pin "2") (pinfunction "2_2") (pintype "passive"))
      (node (ref "C9") (pin "2") (pinfunction "2_2") (pintype "passive"))
      (node (ref "D2") (pin "1") (pinfunction "P$1_1") (pintype "passive"))
      (node (ref "D3") (pin "1") (pinfunction "C_1") (pintype "passive"))
      (node (ref "D4") (pin "1") (pinfunction "C_1") (pintype "passive"))
      (node (ref "J1") (pin "20") (pinfunction "20_20") (pintype "passive"))
      (node (ref "J1") (pin "5") (pinfunction "5_5") (pintype "passive"))
      (node (ref "J2") (pin "23") (pinfunction "23_23") (pintype "passive"))
      (node (ref "J2") (pin "8") (pinfunction "8_8") (pintype "passive"))
      (node (ref "M1") (pin "1") (pinfunction "GND_1") (pintype "power_in"))
      (node (ref "M1") (pin "10") (pinfunction "GND_10") (pintype "power_in"))
      (node (ref "M1") (pin "2") (pinfunction "GND_2") (pintype "power_in"))
      (node (ref "M1") (pin "22") (pinfunction "GND_22") (pintype "power_in"))
      (node (ref "M1") (pin "27") (pinfunction "GND_27") (pintype "power_in"))
      (node (ref "M1") (pin "3") (pinfunction "GND_3") (pintype "power_in"))
      (node (ref "M1") (pin "35") (pinfunction "GND_35") (pintype "power_in"))
      (node (ref "M1") (pin "45") (pinfunction "GND_45") (pintype "power_in"))
      (node (ref "M1") (pin "51") (pinfunction "GND_51") (pintype "power_in"))
      (node (ref "M1") (pin "54") (pinfunction "GND_54") (pintype "power_in"))
      (node (ref "M1") (pin "57") (pinfunction "GND_57") (pintype "power_in"))
      (node (ref "M1") (pin "58") (pinfunction "GND_58") (pintype "power_in"))
      (node (ref "M1") (pin "60") (pinfunction "GND_60") (pintype "power_in"))
      (node (ref "R11") (pin "1") (pinfunction "1_1") (pintype "passive"))
      (node (ref "R2") (pin "1") (pinfunction "1_1") (pintype "passive"))
      (node (ref "R4") (pin "1") (pinfunction "1_1") (pintype "passive"))
      (node (ref "S1") (pin "5") (pinfunction "5_5") (pintype "passive"))
      (node (ref "U1") (pin "3") (pinfunction "AGND_3") (pintype "power_in"))
      (node (ref "U1") (pin "5") (pinfunction "PGND_5") (pintype "power_in"))
      (node (ref "U10") (pin "6") (pinfunction "GND_6") (pintype "power_in"))
      (node (ref "U11") (pin "6") (pinfunction "GND_6") (pintype "power_in"))
      (node (ref "U12") (pin "6") (pinfunction "GND_6") (pintype "power_in"))
      (node (ref "U13") (pin "2") (pinfunction "GND_2") (pintype "power_in"))
      (node (ref "U2") (pin "2") (pinfunction "GND_2") (pintype "power_in"))
      (node (ref "U3") (pin "2") (pinfunction "GND_2") (pintype "power_in"))
      (node (ref "U3") (pin "PAD") (pinfunction "PAD_PAD") (pintype "power_in"))
      (node (ref "U4") (pin "3") (pinfunction "GND_3") (pintype "power_in"))
      (node (ref "U5") (pin "2") (pinfunction "GND_2") (pintype "power_in"))
      (node (ref "U6") (pin "6") (pinfunction "GND_6") (pintype "power_in"))
      (node (ref "U7") (pin "6") (pinfunction "GND_6") (pintype "power_in"))
      (node (ref "U8") (pin "6") (pinfunction "GND_6") (pintype "power_in"))
      (node (ref "U9") (pin "6") (pinfunction "GND_6") (pintype "power_in"))
    )
    (net (code "95") (name "Net-(D3-A)") (class "Default")
      (node (ref "D3") (pin "2") (pinfunction "A_2") (pintype "passive"))
      (node (ref "R6") (pin "1") (pinfunction "1_1") (pintype "passive"))
    )
    (net (code "96") (name "Net-(D4-A)") (class "Default")
      (node (ref "D4") (pin "2") (pinfunction "A_2") (pintype "passive"))
      (node (ref "R9") (pin "1") (pinfunction "1_1") (pintype "passive"))
    )
    (net (code "97") (name "Net-(M1-+2.5VD_OUT)") (class "Default")
      (node (ref "M1") (pin "23") (pinfunction "+2.5VD_OUT_23") (pintype "power_in"))
      (node (ref "R8") (pin "2") (pinfunction "2_2") (pintype "passive"))
    )
    (net (code "98") (name "Net-(M1-+3.3VD_IN-Pad25)") (class "Default")
      (node (ref "M1") (pin "25") (pinfunction "+3.3VD_IN_25") (pintype "power_in"))
      (node (ref "M1") (pin "26") (pinfunction "+3.3VD_IN_26") (pintype "power_in"))
      (node (ref "R6") (pin "2") (pinfunction "2_2") (pintype "passive"))
      (node (ref "R7") (pin "2") (pinfunction "2_2") (pintype "passive"))
    )
    (net (code "99") (name "Net-(TP1-PP)") (class "Default")
      (node (ref "TP1") (pin "1") (pinfunction "PP_1") (pintype "passive"))
      (node (ref "U3") (pin "1") (pinfunction "RI_1") (pintype "input"))
    )
    (net (code "100") (name "Net-(TP3-PP)") (class "Default")
      (node (ref "TP3") (pin "1") (pinfunction "PP_1") (pintype "passive"))
      (node (ref "U3") (pin "11") (pinfunction "GPIO.3_11") (pintype "bidirectional"))
    )
    (net (code "101") (name "Net-(TP4-PP)") (class "Default")
      (node (ref "TP4") (pin "1") (pinfunction "PP_1") (pintype "passive"))
      (node (ref "U3") (pin "12") (pinfunction "GPIO.2_12") (pintype "bidirectional"))
    )
    (net (code "102") (name "Net-(TP5-PP)") (class "Default")
      (node (ref "TP5") (pin "1") (pinfunction "PP_1") (pintype "passive"))
      (node (ref "U3") (pin "13") (pinfunction "GPIO.1_13") (pintype "bidirectional"))
    )
    (net (code "103") (name "Net-(TP6-PP)") (class "Default")
      (node (ref "TP6") (pin "1") (pinfunction "PP_1") (pintype "passive"))
      (node (ref "U3") (pin "14") (pinfunction "GPIO.0_14") (pintype "bidirectional"))
    )
    (net (code "104") (name "Net-(TP7-PP)") (class "Default")
      (node (ref "TP7") (pin "1") (pinfunction "PP_1") (pintype "passive"))
      (node (ref "U3") (pin "18") (pinfunction "CTS_18") (pintype "input"))
    )
    (net (code "105") (name "Net-(TP8-PP)") (class "Default")
      (node (ref "TP8") (pin "1") (pinfunction "PP_1") (pintype "passive"))
      (node (ref "U3") (pin "19") (pinfunction "RTS_19") (pintype "output"))
    )
    (net (code "106") (name "Net-(TP10-PP)") (class "Default")
      (node (ref "TP10") (pin "1") (pinfunction "PP_1") (pintype "passive"))
      (node (ref "U3") (pin "23") (pinfunction "DTR_23") (pintype "output"))
    )
    (net (code "107") (name "Net-(TP11-PP)") (class "Default")
      (node (ref "TP11") (pin "1") (pinfunction "PP_1") (pintype "passive"))
      (node (ref "U3") (pin "24") (pinfunction "DCD_24") (pintype "input"))
    )
    (net (code "108") (name "Net-(U3-VDD)") (class "Default")
      (node (ref "C8") (pin "1") (pinfunction "1_1") (pintype "passive"))
      (node (ref "C9") (pin "1") (pinfunction "1_1") (pintype "passive"))
      (node (ref "U3") (pin "6") (pinfunction "VDD_6") (pintype "power_in"))
    )
    (net (code "109") (name "Net-(U3-VPP)") (class "Default")
      (node (ref "C20") (pin "1") (pinfunction "1_1") (pintype "passive"))
      (node (ref "U3") (pin "16") (pinfunction "VPP_16") (pintype "passive"))
    )
    (net (code "110") (name "PE") (class "Default")
      (node (ref "C1") (pin "1") (pinfunction "1_1") (pintype "passive"))
      (node (ref "S1") (pin "S$1") (pinfunction "M0_S$1") (pintype "passive"))
      (node (ref "S1") (pin "S$2") (pinfunction "M1_S$2") (pintype "passive"))
      (node (ref "S1") (pin "S$3") (pinfunction "M2_S$3") (pintype "passive"))
    )
    (net (code "111") (name "unconnected-(S1-Pad4)") (class "Default")
      (node (ref "S1") (pin "4") (pinfunction "4_4") (pintype "passive"))
    )
    (net (code "112") (name "unconnected-(SW1-Pad2)") (class "Default")
      (node (ref "SW1") (pin "2") (pinfunction "2_2") (pintype "passive"))
    )
    (net (code "113") (name "unconnected-(SW1-Pad4)") (class "Default")
      (node (ref "SW1") (pin "4") (pinfunction "4_4") (pintype "passive"))
    )
    (net (code "114") (name "unconnected-(U1-PG-Pad8)") (class "Default")
      (node (ref "U1") (pin "8") (pinfunction "PG_8") (pintype "open_collector"))
    )
    (net (code "115") (name "unconnected-(U2-NC-Pad4)") (class "Default")
      (node (ref "U2") (pin "4") (pinfunction "NC_4") (pintype "no_connect"))
    )
    (net (code "116") (name "unconnected-(U3-DSR-Pad22)") (class "Default")
      (node (ref "U3") (pin "22") (pinfunction "DSR_22") (pintype "input"))
    )
    (net (code "117") (name "unconnected-(U3-NC-Pad10)") (class "Default")
      (node (ref "U3") (pin "10") (pinfunction "NC_10") (pintype "no_connect"))
    )
    (net (code "118") (name "unconnected-(U3-SUSPEND-Pad17)") (class "Default")
      (node (ref "U3") (pin "17") (pinfunction "SUSPEND_17") (pintype "output"))
    )
    (net (code "119") (name "unconnected-(U3-~{RST}-Pad9)") (class "Default")
      (node (ref "U3") (pin "9") (pinfunction "~{RST}_9") (pintype "bidirectional"))
    )
    (net (code "120") (name "unconnected-(U3-~{SUSPEND}-Pad15)") (class "Default")
      (node (ref "U3") (pin "15") (pinfunction "~{SUSPEND}_15") (pintype "output"))
    )
  )
)
